# GPRS.net
KiCad netlist of a schematic drawn in Altium Designer
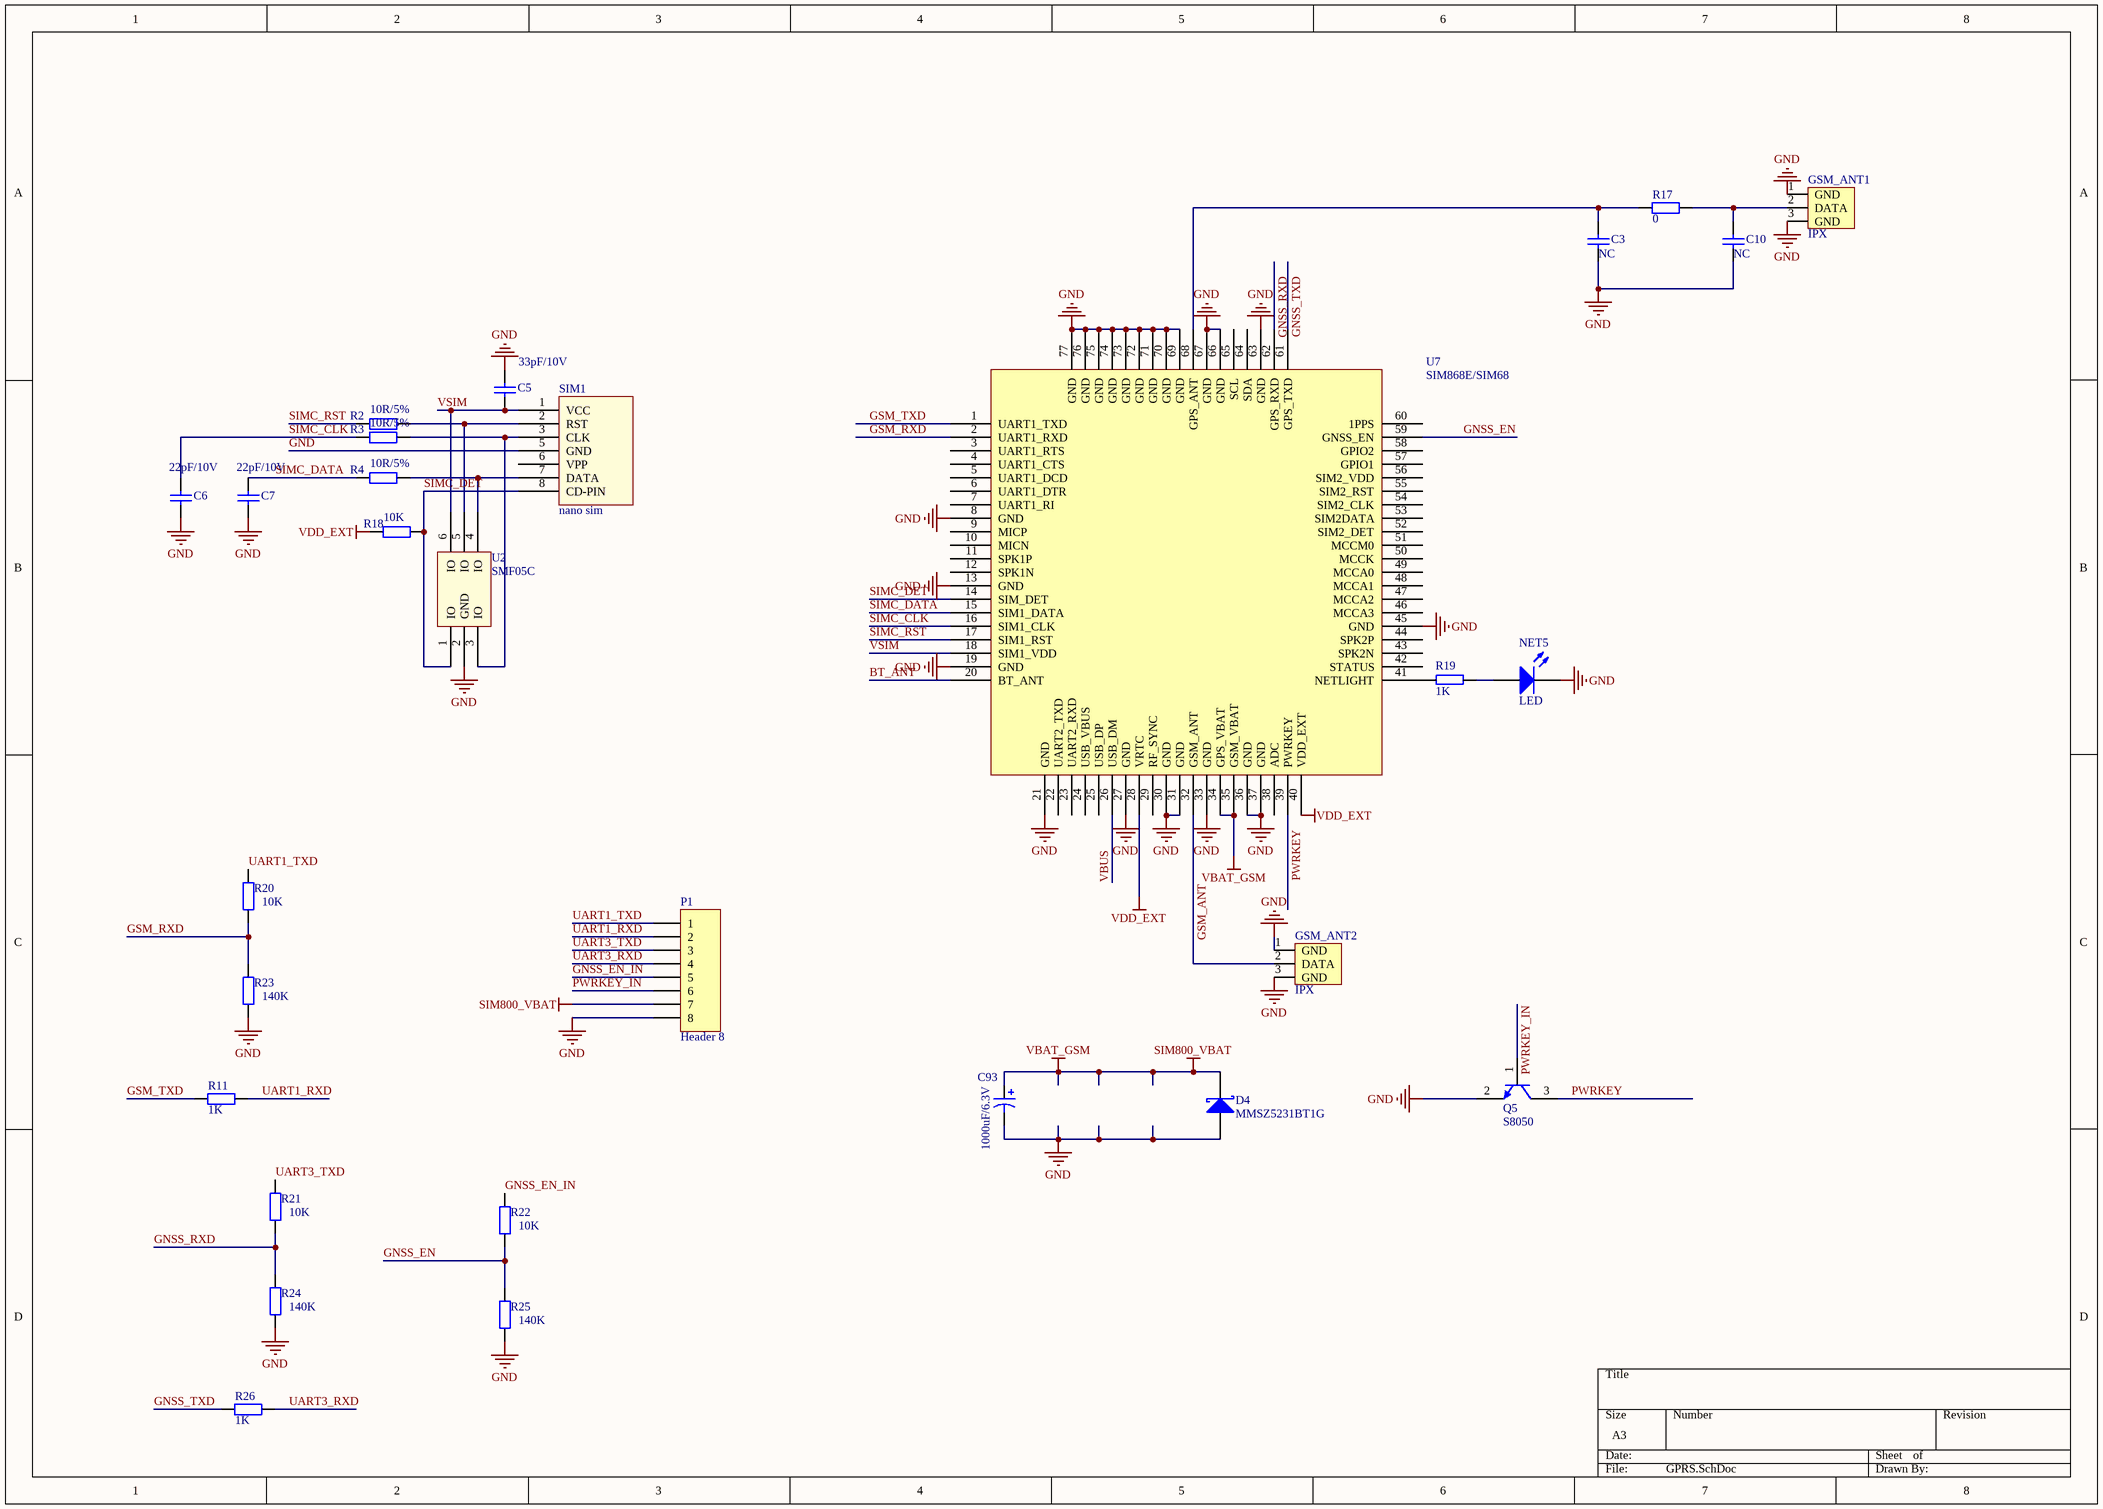
[diagram p0: GPRS.SchDoc]

(export (version "E")
  (design (tool "Eeschema 10.0.6"))
  (components
    (comp (ref "C3")
      (value "NC")
      (footprint "0603C")
      (description "Capacitor")
      (fields (field (name "PUBLISHER") "Altium Limited"))
      (libsource (lib "Miscellaneous Devices") (part "Cap"))
    )
    (comp (ref "C5")
      (value "33pF/10V")
      (footprint "0603C")
      (description "Capacitor")
      (fields (field (name "PUBLISHER") "Altium Limited"))
      (libsource (lib "Miscellaneous Devices") (part "Cap"))
    )
    (comp (ref "C6")
      (value "22pF/10V")
      (footprint "0603C")
      (description "Capacitor")
      (fields (field (name "PUBLISHER") "Altium Limited"))
      (libsource (lib "Miscellaneous Devices") (part "Cap"))
    )
    (comp (ref "C7")
      (value "22pF/10V")
      (footprint "0603C")
      (description "Capacitor")
      (fields (field (name "PUBLISHER") "Altium Limited"))
      (libsource (lib "Miscellaneous Devices") (part "Cap"))
    )
    (comp (ref "C10")
      (value "NC")
      (footprint "0603C")
      (description "Capacitor")
      (fields (field (name "PUBLISHER") "Altium Limited"))
      (libsource (lib "Miscellaneous Devices") (part "Cap"))
    )
    (comp (ref "C93")
      (value "1000uF/6.3V")
      (footprint "7343")
      (description "Polarized Capacitor (Radial)")
      (fields (field (name "PUBLISHER") "Altium Limited"))
      (libsource (lib "Miscellaneous Devices") (part "Cap Pol1"))
    )
    (comp (ref "D4")
      (value "MMSZ5231BT1G")
      (footprint "SOD123")
      (description "Schottky Rectifier")
      (fields (field (name "PUBLISHER") "Altium Limited"))
      (libsource (lib "Miscellaneous Devices") (part "Diode 10TQ040"))
    )
    (comp (ref "GSM_ANT1")
      (value "IPX")
      (footprint "IPX")
      (description "IPEX座")
      (libsource (lib "SIM800C 原理图库") (part "IPEX"))
    )
    (comp (ref "GSM_ANT2")
      (value "IPX")
      (footprint "IPX")
      (description "IPEX座")
      (libsource (lib "SIM800C 原理图库") (part "IPEX"))
    )
    (comp (ref "NET5")
      (value "LED")
      (footprint "0603LED")
      (description "Typical RED, GREEN, YELLOW, AMBER GaAs LED")
      (fields (field (name "PUBLISHER") "Altium Limited"))
      (libsource (lib "SIM800C 原理图库") (part "LED2"))
    )
    (comp (ref "P1")
      (value "Header 8")
      (footprint "HDR1X8")
      (description "Header, 8-Pin")
      (fields (field (name "PUBLISHER") "Altium Limited"))
      (libsource (lib "Miscellaneous Connectors") (part "Header 8"))
    )
    (comp (ref "Q5") (value "S8050") (footprint "SOT23-3") (libsource (lib "Schlib1") (part "NPN")))
    (comp (ref "R2")
      (value "10R/5%")
      (footprint "0603R")
      (description "Resistor")
      (fields (field (name "PUBLISHER") "Altium Limited"))
      (libsource (lib "Miscellaneous Devices") (part "Res2"))
    )
    (comp (ref "R3")
      (value "10R/5%")
      (footprint "0603R")
      (description "Resistor")
      (fields (field (name "PUBLISHER") "Altium Limited"))
      (libsource (lib "Miscellaneous Devices") (part "Res2"))
    )
    (comp (ref "R4")
      (value "10R/5%")
      (footprint "0603R")
      (description "Resistor")
      (fields (field (name "PUBLISHER") "Altium Limited"))
      (libsource (lib "Miscellaneous Devices") (part "Res2"))
    )
    (comp (ref "R11")
      (value "1K")
      (footprint "0603R")
      (description "Resistor")
      (fields (field (name "PUBLISHER") "Altium Limited"))
      (libsource (lib "") (part "Res2_2"))
    )
    (comp (ref "R17")
      (value "0")
      (footprint "0603R")
      (description "Resistor")
      (fields (field (name "PUBLISHER") "Altium Limited"))
      (libsource (lib "") (part "Res2_2"))
    )
    (comp (ref "R18")
      (value "10K")
      (footprint "0603R")
      (description "Resistor")
      (fields (field (name "PUBLISHER") "Altium Limited"))
      (libsource (lib "Miscellaneous Devices") (part "Res2"))
    )
    (comp (ref "R19") (value "1K") (footprint "0603r") (libsource (lib "SIM800C 原理图库") (part "R")))
    (comp (ref "R20")
      (value "10K")
      (footprint "0603R")
      (description "Resistor")
      (fields (field (name "PUBLISHER") "Altium Limited"))
      (libsource (lib "") (part "Res2_1"))
    )
    (comp (ref "R21")
      (value "10K")
      (footprint "0603R")
      (description "Resistor")
      (fields (field (name "PUBLISHER") "Altium Limited"))
      (libsource (lib "") (part "Res2_1"))
    )
    (comp (ref "R22")
      (value "10K")
      (footprint "0603R")
      (description "Resistor")
      (fields (field (name "PUBLISHER") "Altium Limited"))
      (libsource (lib "") (part "Res2_1"))
    )
    (comp (ref "R23")
      (value "140K")
      (footprint "0603R")
      (description "Resistor")
      (fields (field (name "PUBLISHER") "Altium Limited"))
      (libsource (lib "") (part "Res2_1"))
    )
    (comp (ref "R24")
      (value "140K")
      (footprint "0603R")
      (description "Resistor")
      (fields (field (name "PUBLISHER") "Altium Limited"))
      (libsource (lib "") (part "Res2_1"))
    )
    (comp (ref "R25")
      (value "140K")
      (footprint "0603R")
      (description "Resistor")
      (fields (field (name "PUBLISHER") "Altium Limited"))
      (libsource (lib "") (part "Res2_1"))
    )
    (comp (ref "R26")
      (value "1K")
      (footprint "0603R")
      (description "Resistor")
      (fields (field (name "PUBLISHER") "Altium Limited"))
      (libsource (lib "") (part "Res2_2"))
    )
    (comp (ref "SIM1") (value "nano sim") (footprint "Nano SIM") (libsource (lib "lm") (part "nano sim")))
    (comp (ref "U2") (value "SMF05C") (footprint "SC70-6L") (libsource (lib "lm") (part "SMF05C")))
    (comp (ref "U7")
      (value "SIM868E/SIM68")
      (footprint "SIM868")
      (libsource (lib "stm32") (part "SIM868E/SIM868"))
    )
  )
  (nets
    (net (code "1") (name "/BT_ANT") (class "Default")
      (node (ref "U7") (pin "20") (pinfunction "BT_ANT_20") (pintype "passive"))
    )
    (net (code "2") (name "/GNSS_EN") (class "Default")
      (node (ref "R22") (pin "2") (pinfunction "2_2") (pintype "passive"))
      (node (ref "R25") (pin "1") (pinfunction "1_1") (pintype "passive"))
      (node (ref "U7") (pin "59") (pinfunction "GNSS_EN_59") (pintype "passive"))
    )
    (net (code "3") (name "/GNSS_EN_IN") (class "Default")
      (node (ref "P1") (pin "5") (pinfunction "5_5") (pintype "passive"))
      (node (ref "R22") (pin "1") (pinfunction "1_1") (pintype "passive"))
    )
    (net (code "4") (name "/GNSS_RXD") (class "Default")
      (node (ref "R21") (pin "2") (pinfunction "2_2") (pintype "passive"))
      (node (ref "R24") (pin "1") (pinfunction "1_1") (pintype "passive"))
      (node (ref "U7") (pin "62") (pinfunction "GPS_RXD_62") (pintype "passive"))
    )
    (net (code "5") (name "/GNSS_TXD") (class "Default")
      (node (ref "R26") (pin "1") (pinfunction "1_1") (pintype "passive"))
      (node (ref "U7") (pin "61") (pinfunction "GPS_TXD_61") (pintype "passive"))
    )
    (net (code "6") (name "/GSM_ANT") (class "Default")
      (node (ref "GSM_ANT2") (pin "2") (pinfunction "DATA_2") (pintype "passive"))
      (node (ref "U7") (pin "32") (pinfunction "GSM_ANT_32") (pintype "passive"))
    )
    (net (code "7") (name "/GSM_RXD") (class "Default")
      (node (ref "R20") (pin "2") (pinfunction "2_2") (pintype "passive"))
      (node (ref "R23") (pin "1") (pinfunction "1_1") (pintype "passive"))
      (node (ref "U7") (pin "2") (pinfunction "UART1_RXD_2") (pintype "passive"))
    )
    (net (code "8") (name "/GSM_TXD") (class "Default")
      (node (ref "R11") (pin "1") (pinfunction "1_1") (pintype "passive"))
      (node (ref "U7") (pin "1") (pinfunction "UART1_TXD_1") (pintype "passive"))
    )
    (net (code "9") (name "/PWRKEY") (class "Default")
      (node (ref "Q5") (pin "3") (pinfunction "C_3") (pintype "passive"))
      (node (ref "U7") (pin "39") (pinfunction "PWRKEY_39") (pintype "passive"))
    )
    (net (code "10") (name "/PWRKEY_IN") (class "Default")
      (node (ref "P1") (pin "6") (pinfunction "6_6") (pintype "passive"))
      (node (ref "Q5") (pin "1") (pinfunction "B_1") (pintype "passive"))
    )
    (net (code "11") (name "/SIMC_CLK") (class "Default")
      (node (ref "C6") (pin "1") (pinfunction "1_1") (pintype "passive"))
      (node (ref "R3") (pin "2") (pinfunction "2_2") (pintype "passive"))
      (node (ref "U7") (pin "16") (pinfunction "SIM1_CLK_16") (pintype "passive"))
    )
    (net (code "12") (name "/SIMC_DATA") (class "Default")
      (node (ref "C7") (pin "1") (pinfunction "1_1") (pintype "passive"))
      (node (ref "R4") (pin "2") (pinfunction "2_2") (pintype "passive"))
      (node (ref "U7") (pin "15") (pinfunction "SIM1_DATA_15") (pintype "passive"))
    )
    (net (code "13") (name "/SIMC_DET") (class "Default")
      (node (ref "R18") (pin "1") (pinfunction "1_1") (pintype "passive"))
      (node (ref "SIM1") (pin "8") (pinfunction "CD-PIN_8") (pintype "passive"))
      (node (ref "U2") (pin "1") (pinfunction "IO_1") (pintype "passive"))
      (node (ref "U7") (pin "14") (pinfunction "SIM_DET_14") (pintype "passive"))
    )
    (net (code "14") (name "/SIMC_RST") (class "Default")
      (node (ref "R2") (pin "2") (pinfunction "2_2") (pintype "passive"))
      (node (ref "U7") (pin "17") (pinfunction "SIM1_RST_17") (pintype "passive"))
    )
    (net (code "15") (name "/UART1_RXD") (class "Default")
      (node (ref "P1") (pin "2") (pinfunction "2_2") (pintype "passive"))
      (node (ref "R11") (pin "2") (pinfunction "2_2") (pintype "passive"))
    )
    (net (code "16") (name "/UART1_TXD") (class "Default")
      (node (ref "P1") (pin "1") (pinfunction "1_1") (pintype "passive"))
      (node (ref "R20") (pin "1") (pinfunction "1_1") (pintype "passive"))
    )
    (net (code "17") (name "/UART3_RXD") (class "Default")
      (node (ref "P1") (pin "4") (pinfunction "4_4") (pintype "passive"))
      (node (ref "R26") (pin "2") (pinfunction "2_2") (pintype "passive"))
    )
    (net (code "18") (name "/UART3_TXD") (class "Default")
      (node (ref "P1") (pin "3") (pinfunction "3_3") (pintype "passive"))
      (node (ref "R21") (pin "1") (pinfunction "1_1") (pintype "passive"))
    )
    (net (code "19") (name "/VBUS") (class "Default")
      (node (ref "U7") (pin "26") (pinfunction "USB_DM_26") (pintype "passive"))
    )
    (net (code "20") (name "/VSIM") (class "Default")
      (node (ref "C5") (pin "2") (pinfunction "2_2") (pintype "passive"))
      (node (ref "SIM1") (pin "1") (pinfunction "VCC_1") (pintype "passive"))
      (node (ref "U2") (pin "6") (pinfunction "IO_6") (pintype "passive"))
      (node (ref "U7") (pin "18") (pinfunction "SIM1_VDD_18") (pintype "passive"))
    )
    (net (code "21") (name "GND") (class "Default")
      (node (ref "C10") (pin "2") (pinfunction "2_2") (pintype "passive"))
      (node (ref "C3") (pin "2") (pinfunction "2_2") (pintype "passive"))
      (node (ref "C5") (pin "1") (pinfunction "1_1") (pintype "passive"))
      (node (ref "C6") (pin "2") (pinfunction "2_2") (pintype "passive"))
      (node (ref "C7") (pin "2") (pinfunction "2_2") (pintype "passive"))
      (node (ref "C93") (pin "2") (pinfunction "2_2") (pintype "passive"))
      (node (ref "D4") (pin "1") (pinfunction "A_1") (pintype "passive"))
      (node (ref "GSM_ANT1") (pin "1") (pinfunction "GND_1") (pintype "passive"))
      (node (ref "GSM_ANT1") (pin "3") (pinfunction "GND_3") (pintype "passive"))
      (node (ref "GSM_ANT2") (pin "1") (pinfunction "GND_1") (pintype "passive"))
      (node (ref "GSM_ANT2") (pin "3") (pinfunction "GND_3") (pintype "passive"))
      (node (ref "NET5") (pin "2") (pinfunction "K_2") (pintype "passive"))
      (node (ref "P1") (pin "8") (pinfunction "8_8") (pintype "passive"))
      (node (ref "Q5") (pin "2") (pinfunction "E_2") (pintype "passive"))
      (node (ref "R23") (pin "2") (pinfunction "2_2") (pintype "passive"))
      (node (ref "R24") (pin "2") (pinfunction "2_2") (pintype "passive"))
      (node (ref "R25") (pin "2") (pinfunction "2_2") (pintype "passive"))
      (node (ref "SIM1") (pin "5") (pinfunction "GND_5") (pintype "passive"))
      (node (ref "U2") (pin "2") (pinfunction "GND_2") (pintype "passive"))
      (node (ref "U7") (pin "13") (pinfunction "GND_13") (pintype "passive"))
      (node (ref "U7") (pin "19") (pinfunction "GND_19") (pintype "passive"))
      (node (ref "U7") (pin "21") (pinfunction "GND_21") (pintype "passive"))
      (node (ref "U7") (pin "27") (pinfunction "GND_27") (pintype "passive"))
      (node (ref "U7") (pin "30") (pinfunction "GND_30") (pintype "passive"))
      (node (ref "U7") (pin "31") (pinfunction "GND_31") (pintype "passive"))
      (node (ref "U7") (pin "33") (pinfunction "GND_33") (pintype "passive"))
      (node (ref "U7") (pin "36") (pinfunction "GND_36") (pintype "passive"))
      (node (ref "U7") (pin "37") (pinfunction "GND_37") (pintype "passive"))
      (node (ref "U7") (pin "45") (pinfunction "GND_45") (pintype "passive"))
      (node (ref "U7") (pin "63") (pinfunction "GND_63") (pintype "passive"))
      (node (ref "U7") (pin "66") (pinfunction "GND_66") (pintype "passive"))
      (node (ref "U7") (pin "67") (pinfunction "GND_67") (pintype "passive"))
      (node (ref "U7") (pin "69") (pinfunction "GND_69") (pintype "passive"))
      (node (ref "U7") (pin "70") (pinfunction "GND_70") (pintype "passive"))
      (node (ref "U7") (pin "71") (pinfunction "GND_71") (pintype "passive"))
      (node (ref "U7") (pin "72") (pinfunction "GND_72") (pintype "passive"))
      (node (ref "U7") (pin "73") (pinfunction "GND_73") (pintype "passive"))
      (node (ref "U7") (pin "74") (pinfunction "GND_74") (pintype "passive"))
      (node (ref "U7") (pin "75") (pinfunction "GND_75") (pintype "passive"))
      (node (ref "U7") (pin "76") (pinfunction "GND_76") (pintype "passive"))
      (node (ref "U7") (pin "77") (pinfunction "GND_77") (pintype "passive"))
      (node (ref "U7") (pin "8") (pinfunction "GND_8") (pintype "passive"))
    )
    (net (code "22") (name "Net-(GSM_ANT1-DATA)") (class "Default")
      (node (ref "C10") (pin "1") (pinfunction "1_1") (pintype "passive"))
      (node (ref "GSM_ANT1") (pin "2") (pinfunction "DATA_2") (pintype "passive"))
      (node (ref "R17") (pin "2") (pinfunction "2_2") (pintype "passive"))
    )
    (net (code "23") (name "Net-(NET5-A)") (class "Default")
      (node (ref "NET5") (pin "1") (pinfunction "A_1") (pintype "passive"))
      (node (ref "R19") (pin "1") (pintype "passive"))
    )
    (net (code "24") (name "Net-(SIM1-CLK)") (class "Default")
      (node (ref "R3") (pin "1") (pinfunction "1_1") (pintype "passive"))
      (node (ref "SIM1") (pin "3") (pinfunction "CLK_3") (pintype "passive"))
      (node (ref "U2") (pin "3") (pinfunction "IO_3") (pintype "passive"))
    )
    (net (code "25") (name "Net-(SIM1-DATA)") (class "Default")
      (node (ref "R4") (pin "1") (pinfunction "1_1") (pintype "passive"))
      (node (ref "SIM1") (pin "7") (pinfunction "DATA_7") (pintype "passive"))
      (node (ref "U2") (pin "4") (pinfunction "IO_4") (pintype "passive"))
    )
    (net (code "26") (name "Net-(SIM1-RST)") (class "Default")
      (node (ref "R2") (pin "1") (pinfunction "1_1") (pintype "passive"))
      (node (ref "SIM1") (pin "2") (pinfunction "RST_2") (pintype "passive"))
      (node (ref "U2") (pin "5") (pinfunction "IO_5") (pintype "passive"))
    )
    (net (code "27") (name "Net-(U7-GPS_ANT)") (class "Default")
      (node (ref "C3") (pin "1") (pinfunction "1_1") (pintype "passive"))
      (node (ref "R17") (pin "1") (pinfunction "1_1") (pintype "passive"))
      (node (ref "U7") (pin "68") (pinfunction "GPS_ANT_68") (pintype "passive"))
    )
    (net (code "28") (name "Net-(U7-NETLIGHT)") (class "Default")
      (node (ref "R19") (pin "2") (pintype "passive"))
      (node (ref "U7") (pin "41") (pinfunction "NETLIGHT_41") (pintype "passive"))
    )
    (net (code "29") (name "SIM800_VBAT") (class "Default")
      (node (ref "C93") (pin "1") (pinfunction "1_1") (pintype "passive"))
      (node (ref "D4") (pin "2") (pinfunction "K_2") (pintype "passive"))
      (node (ref "P1") (pin "7") (pinfunction "7_7") (pintype "passive"))
      (node (ref "U7") (pin "34") (pinfunction "GPS_VBAT_34") (pintype "passive"))
      (node (ref "U7") (pin "35") (pinfunction "GSM_VBAT_35") (pintype "passive"))
    )
    (net (code "30") (name "VDD_EXT") (class "Default")
      (node (ref "R18") (pin "2") (pinfunction "2_2") (pintype "passive"))
      (node (ref "U7") (pin "28") (pinfunction "VRTC_28") (pintype "passive"))
      (node (ref "U7") (pin "40") (pinfunction "VDD_EXT_40") (pintype "passive"))
    )
    (net (code "31") (name "unconnected-(SIM1-VPP-Pad6)") (class "Default")
      (node (ref "SIM1") (pin "6") (pinfunction "VPP_6") (pintype "passive"))
    )
    (net (code "32") (name "unconnected-(U7-1PPS-Pad60)") (class "Default")
      (node (ref "U7") (pin "60") (pinfunction "1PPS_60") (pintype "passive"))
    )
    (net (code "33") (name "unconnected-(U7-ADC-Pad38)") (class "Default")
      (node (ref "U7") (pin "38") (pinfunction "ADC_38") (pintype "passive"))
    )
    (net (code "34") (name "unconnected-(U7-GPIO1-Pad57)") (class "Default")
      (node (ref "U7") (pin "57") (pinfunction "GPIO1_57") (pintype "passive"))
    )
    (net (code "35") (name "unconnected-(U7-GPIO2-Pad58)") (class "Default")
      (node (ref "U7") (pin "58") (pinfunction "GPIO2_58") (pintype "passive"))
    )
    (net (code "36") (name "unconnected-(U7-MCCA0-Pad49)") (class "Default")
      (node (ref "U7") (pin "49") (pinfunction "MCCA0_49") (pintype "passive"))
    )
    (net (code "37") (name "unconnected-(U7-MCCA1-Pad48)") (class "Default")
      (node (ref "U7") (pin "48") (pinfunction "MCCA1_48") (pintype "passive"))
    )
    (net (code "38") (name "unconnected-(U7-MCCA2-Pad47)") (class "Default")
      (node (ref "U7") (pin "47") (pinfunction "MCCA2_47") (pintype "passive"))
    )
    (net (code "39") (name "unconnected-(U7-MCCA3-Pad46)") (class "Default")
      (node (ref "U7") (pin "46") (pinfunction "MCCA3_46") (pintype "passive"))
    )
    (net (code "40") (name "unconnected-(U7-MCCK-Pad50)") (class "Default")
      (node (ref "U7") (pin "50") (pinfunction "MCCK_50") (pintype "passive"))
    )
    (net (code "41") (name "unconnected-(U7-MCCM0-Pad51)") (class "Default")
      (node (ref "U7") (pin "51") (pinfunction "MCCM0_51") (pintype "passive"))
    )
    (net (code "42") (name "unconnected-(U7-MICN-Pad10)") (class "Default")
      (node (ref "U7") (pin "10") (pinfunction "MICN_10") (pintype "passive"))
    )
    (net (code "43") (name "unconnected-(U7-MICP-Pad9)") (class "Default")
      (node (ref "U7") (pin "9") (pinfunction "MICP_9") (pintype "passive"))
    )
    (net (code "44") (name "unconnected-(U7-RF_SYNC-Pad29)") (class "Default")
      (node (ref "U7") (pin "29") (pinfunction "RF_SYNC_29") (pintype "passive"))
    )
    (net (code "45") (name "unconnected-(U7-SCL-Pad65)") (class "Default")
      (node (ref "U7") (pin "65") (pinfunction "SCL_65") (pintype "passive"))
    )
    (net (code "46") (name "unconnected-(U7-SDA-Pad64)") (class "Default")
      (node (ref "U7") (pin "64") (pinfunction "SDA_64") (pintype "passive"))
    )
    (net (code "47") (name "unconnected-(U7-SIM2DATA-Pad53)") (class "Default")
      (node (ref "U7") (pin "53") (pinfunction "SIM2DATA_53") (pintype "passive"))
    )
    (net (code "48") (name "unconnected-(U7-SIM2_CLK-Pad54)") (class "Default")
      (node (ref "U7") (pin "54") (pinfunction "SIM2_CLK_54") (pintype "passive"))
    )
    (net (code "49") (name "unconnected-(U7-SIM2_DET-Pad52)") (class "Default")
      (node (ref "U7") (pin "52") (pinfunction "SIM2_DET_52") (pintype "passive"))
    )
    (net (code "50") (name "unconnected-(U7-SIM2_RST-Pad55)") (class "Default")
      (node (ref "U7") (pin "55") (pinfunction "SIM2_RST_55") (pintype "passive"))
    )
    (net (code "51") (name "unconnected-(U7-SIM2_VDD-Pad56)") (class "Default")
      (node (ref "U7") (pin "56") (pinfunction "SIM2_VDD_56") (pintype "passive"))
    )
    (net (code "52") (name "unconnected-(U7-SPK1N-Pad12)") (class "Default")
      (node (ref "U7") (pin "12") (pinfunction "SPK1N_12") (pintype "passive"))
    )
    (net (code "53") (name "unconnected-(U7-SPK1P-Pad11)") (class "Default")
      (node (ref "U7") (pin "11") (pinfunction "SPK1P_11") (pintype "passive"))
    )
    (net (code "54") (name "unconnected-(U7-SPK2N-Pad43)") (class "Default")
      (node (ref "U7") (pin "43") (pinfunction "SPK2N_43") (pintype "passive"))
    )
    (net (code "55") (name "unconnected-(U7-SPK2P-Pad44)") (class "Default")
      (node (ref "U7") (pin "44") (pinfunction "SPK2P_44") (pintype "passive"))
    )
    (net (code "56") (name "unconnected-(U7-STATUS-Pad42)") (class "Default")
      (node (ref "U7") (pin "42") (pinfunction "STATUS_42") (pintype "passive"))
    )
    (net (code "57") (name "unconnected-(U7-UART1_CTS-Pad4)") (class "Default")
      (node (ref "U7") (pin "4") (pinfunction "UART1_CTS_4") (pintype "passive"))
    )
    (net (code "58") (name "unconnected-(U7-UART1_DCD-Pad5)") (class "Default")
      (node (ref "U7") (pin "5") (pinfunction "UART1_DCD_5") (pintype "passive"))
    )
    (net (code "59") (name "unconnected-(U7-UART1_DTR-Pad6)") (class "Default")
      (node (ref "U7") (pin "6") (pinfunction "UART1_DTR_6") (pintype "passive"))
    )
    (net (code "60") (name "unconnected-(U7-UART1_RI-Pad7)") (class "Default")
      (node (ref "U7") (pin "7") (pinfunction "UART1_RI_7") (pintype "passive"))
    )
    (net (code "61") (name "unconnected-(U7-UART1_RTS-Pad3)") (class "Default")
      (node (ref "U7") (pin "3") (pinfunction "UART1_RTS_3") (pintype "passive"))
    )
    (net (code "62") (name "unconnected-(U7-UART2_RXD-Pad23)") (class "Default")
      (node (ref "U7") (pin "23") (pinfunction "UART2_RXD_23") (pintype "passive"))
    )
    (net (code "63") (name "unconnected-(U7-UART2_TXD-Pad22)") (class "Default")
      (node (ref "U7") (pin "22") (pinfunction "UART2_TXD_22") (pintype "passive"))
    )
    (net (code "64") (name "unconnected-(U7-USB_DP-Pad25)") (class "Default")
      (node (ref "U7") (pin "25") (pinfunction "USB_DP_25") (pintype "passive"))
    )
    (net (code "65") (name "unconnected-(U7-USB_VBUS-Pad24)") (class "Default")
      (node (ref "U7") (pin "24") (pinfunction "USB_VBUS_24") (pintype "passive"))
    )
  )
)
